# HeatPlatform_V1.net
KiCad netlist of a schematic drawn in Altium Designer
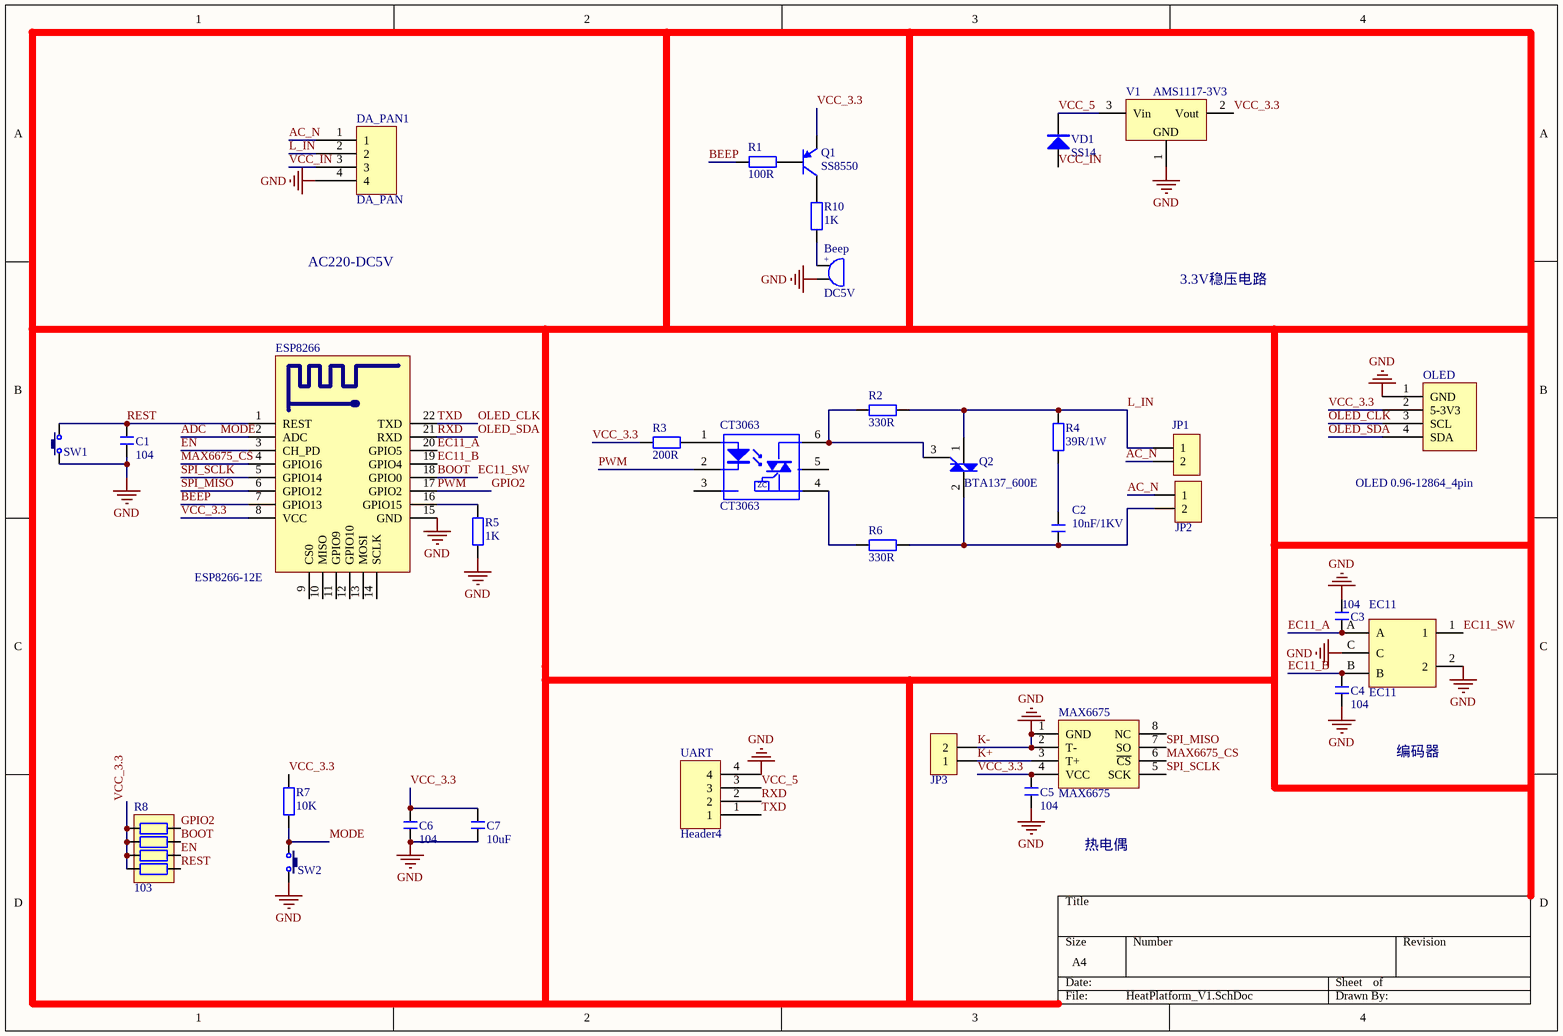
[diagram p0: HeatPlatform_V1.SchDoc]

(export (version "E")
  (design (tool "Eeschema 10.0.6"))
  (components
    (comp (ref "Beep")
      (value "DC5V")
      (footprint "BEEP 5x9x5.5")
      (description "蜂鸣器")
      (fields (field (name "版权归属") "源创客"))
      (libsource (lib "HeatPlatform") (part "BEEP"))
    )
    (comp (ref "C1")
      (value "104")
      (footprint "C 0603")
      (description "无极性贴片电容")
      (fields (field (name "版权归属") "源创客"))
      (libsource (lib "HeatPlatform") (part "C"))
    )
    (comp (ref "C2")
      (value "10nF/1KV")
      (footprint "C 1210_L")
      (description "无极性贴片电容")
      (fields (field (name "版权归属") "源创客"))
      (libsource (lib "HeatPlatform") (part "C"))
    )
    (comp (ref "C3")
      (value "104")
      (footprint "C 0603")
      (description "无极性贴片电容")
      (fields (field (name "版权归属") "源创客"))
      (libsource (lib "HeatPlatform") (part "C"))
    )
    (comp (ref "C4")
      (value "104")
      (footprint "C 0603")
      (description "无极性贴片电容")
      (fields (field (name "版权归属") "源创客"))
      (libsource (lib "HeatPlatform") (part "C"))
    )
    (comp (ref "C5")
      (value "104")
      (footprint "C 0603")
      (description "无极性贴片电容")
      (fields (field (name "版权归属") "源创客"))
      (libsource (lib "HeatPlatform") (part "C"))
    )
    (comp (ref "C6")
      (value "104")
      (footprint "C 0603")
      (description "无极性贴片电容")
      (fields (field (name "版权归属") "源创客"))
      (libsource (lib "HeatPlatform") (part "C"))
    )
    (comp (ref "C7")
      (value "10uF")
      (footprint "C 0603")
      (description "无极性贴片电容")
      (fields (field (name "版权归属") "源创客"))
      (libsource (lib "HeatPlatform") (part "C"))
    )
    (comp (ref "CT3063")
      (value "CT3063")
      (footprint "SMD-6")
      (description "线性光耦（过零检测）")
      (fields (field (name "版权归属") "源创客"))
      (libsource (lib "HeatPlatform") (part "CT3063"))
    )
    (comp (ref "DA_PAN1")
      (value "DA_PAN")
      (footprint "DA_PAN")
      (libsource (lib "HeatPlatform") (part "DA_PAN"))
    )
    (comp (ref "EC11")
      (value "EC11")
      (footprint "EC11")
      (description "数字开关编码器")
      (fields (field (name "版权归属") "源创客"))
      (libsource (lib "HeatPlatform") (part "EC11"))
    )
    (comp (ref "ESP8266")
      (value "ESP8266-12E")
      (footprint "ESP_12E")
      (description "串口 WIFI模块，ESP-12E")
      (fields (field (name "版权归属") "源创客"))
      (libsource (lib "HeatPlatform") (part "ESP8266-12E"))
    )
    (comp (ref "JP1")
      (value "HDR-1X2")
      (footprint "HDR-1X2")
      (description "2P接插件")
      (fields (field (name "版权归属") "源创客"))
      (libsource (lib "") (part "Header 2_1"))
    )
    (comp (ref "JP2")
      (value "HDR-1X2")
      (footprint "HDR-1X2")
      (description "2P接插件")
      (fields (field (name "版权归属") "源创客"))
      (libsource (lib "") (part "Header 2_1"))
    )
    (comp (ref "JP3")
      (value "HDR-1X2")
      (footprint "HDR-1X2")
      (description "2P接插件")
      (fields (field (name "版权归属") "源创客"))
      (libsource (lib "HeatPlatform") (part "Header 2"))
    )
    (comp (ref "MAX6675")
      (value "MAX6675")
      (footprint "SOP8_L")
      (description "K型热电偶检测芯片")
      (fields (field (name "版权归属") "源创客"))
      (libsource (lib "HeatPlatform") (part "MAX6675"))
    )
    (comp (ref "OLED")
      (value "OLED 0.96-12864_4pin")
      (footprint "OLED 0.96-12864_4pin")
      (description "12864 点阵屏")
      (libsource (lib "HeatPlatform") (part "OLED 0.96-12864_4pin"))
    )
    (comp (ref "Q1")
      (value "SS8550")
      (footprint "SOT23-3L")
      (description "高频放大-PNP型")
      (fields (field (name "版权归属") "源创客"))
      (libsource (lib "HeatPlatform") (part "8550-SMD"))
    )
    (comp (ref "Q2")
      (value "BTA137_600E")
      (footprint "TO252")
      (description "双向可控硅")
      (fields (field (name "版权归属") "源创客"))
      (libsource (lib "HeatPlatform") (part "BTA12_600"))
    )
    (comp (ref "R1")
      (value "100R")
      (footprint "R 0603")
      (description "贴片电阻")
      (fields (field (name "版权归属") "源创客"))
      (libsource (lib "HeatPlatform") (part "R"))
    )
    (comp (ref "R2")
      (value "330R")
      (footprint "R 0603")
      (description "贴片电阻")
      (fields (field (name "版权归属") "源创客"))
      (libsource (lib "HeatPlatform") (part "R"))
    )
    (comp (ref "R3")
      (value "200R")
      (footprint "R 0603")
      (description "贴片电阻")
      (fields (field (name "版权归属") "源创客"))
      (libsource (lib "HeatPlatform") (part "R"))
    )
    (comp (ref "R4")
      (value "39R/1W")
      (footprint "R 2512_L")
      (description "贴片电阻")
      (fields (field (name "版权归属") "源创客"))
      (libsource (lib "HeatPlatform") (part "R"))
    )
    (comp (ref "R5")
      (value "1K")
      (footprint "R 0603")
      (description "贴片电阻")
      (fields (field (name "版权归属") "源创客"))
      (libsource (lib "HeatPlatform") (part "R"))
    )
    (comp (ref "R6")
      (value "330R")
      (footprint "R 0603")
      (description "贴片电阻")
      (fields (field (name "版权归属") "源创客"))
      (libsource (lib "HeatPlatform") (part "R"))
    )
    (comp (ref "R7")
      (value "10K")
      (footprint "R 0603")
      (description "贴片电阻")
      (fields (field (name "版权归属") "源创客"))
      (libsource (lib "HeatPlatform") (part "R"))
    )
    (comp (ref "R8")
      (value "103")
      (footprint "RCA-8P4R-0603")
      (description "贴片网络排阻")
      (fields (field (name "版权归属") "源创客"))
      (libsource (lib "HeatPlatform") (part "R-8P4R"))
    )
    (comp (ref "R10")
      (value "1K")
      (footprint "R 0603")
      (description "贴片电阻")
      (fields (field (name "版权归属") "源创客"))
      (libsource (lib "HeatPlatform") (part "R"))
    )
    (comp (ref "SW1")
      (value "3*4*2")
      (footprint "TSW SMD-3*4*2")
      (description "3x4轻触开关")
      (fields (field (name "版权归属") "源创客"))
      (libsource (lib "") (part "TSW 3x4_1"))
    )
    (comp (ref "SW2")
      (value "3*4*2")
      (footprint "TSW SMD-3*4*2")
      (description "3x4轻触开关")
      (fields (field (name "版权归属") "源创客"))
      (libsource (lib "HeatPlatform") (part "TSW 3x4"))
    )
    (comp (ref "UART")
      (value "Header4")
      (footprint "HDR2.54-LI-4P")
      (libsource (lib "HeatPlatform") (part "Header4"))
    )
    (comp (ref "V1")
      (value "AMS1117-3V3")
      (footprint "SOT223_L")
      (description "三端稳压芯片")
      (fields (field (name "版权归属") "源创客"))
      (libsource (lib "HeatPlatform") (part "AMS1117"))
    )
    (comp (ref "VD1")
      (value "SS14")
      (footprint "SMA")
      (description "肖特基二极管")
      (fields (field (name "版权归属") "源创客"))
      (libsource (lib "HeatPlatform") (part "SS14"))
    )
  )
  (nets
    (net (code "1") (name "/AC_N") (class "Default")
      (node (ref "DA_PAN1") (pin "1") (pinfunction "1_1") (pintype "passive"))
      (node (ref "JP1") (pin "2") (pinfunction "2_2") (pintype "passive"))
      (node (ref "JP2") (pin "1") (pinfunction "1_1") (pintype "passive"))
    )
    (net (code "2") (name "/ADC") (class "Default")
      (node (ref "ESP8266") (pin "2") (pinfunction "ADC_2") (pintype "passive"))
      (node (ref "R7") (pin "1") (pinfunction "1_1") (pintype "passive"))
      (node (ref "SW2") (pin "1") (pinfunction "1_1") (pintype "passive"))
    )
    (net (code "3") (name "/BEEP") (class "Default")
      (node (ref "ESP8266") (pin "7") (pinfunction "GPIO13_7") (pintype "passive"))
      (node (ref "R1") (pin "1") (pinfunction "1_1") (pintype "passive"))
    )
    (net (code "4") (name "/BOOT") (class "Default")
      (node (ref "EC11") (pin "1") (pinfunction "1_1") (pintype "passive"))
      (node (ref "ESP8266") (pin "18") (pinfunction "GPIO0_18") (pintype "passive"))
      (node (ref "R8") (pin "7") (pinfunction "7_7") (pintype "passive"))
    )
    (net (code "5") (name "/EC11_A") (class "Default")
      (node (ref "C3") (pin "1") (pinfunction "1_1") (pintype "passive"))
      (node (ref "EC11") (pin "A") (pinfunction "A_A") (pintype "passive"))
      (node (ref "ESP8266") (pin "20") (pinfunction "GPIO5_20") (pintype "passive"))
    )
    (net (code "6") (name "/EC11_B") (class "Default")
      (node (ref "C4") (pin "2") (pinfunction "2_2") (pintype "passive"))
      (node (ref "EC11") (pin "B") (pinfunction "B_B") (pintype "passive"))
      (node (ref "ESP8266") (pin "19") (pinfunction "GPIO4_19") (pintype "passive"))
    )
    (net (code "7") (name "/EN") (class "Default")
      (node (ref "ESP8266") (pin "3") (pinfunction "CH_PD_3") (pintype "passive"))
      (node (ref "R8") (pin "6") (pinfunction "6_6") (pintype "passive"))
    )
    (net (code "8") (name "/GPIO2") (class "Default")
      (node (ref "CT3063") (pin "2") (pinfunction "C_2") (pintype "passive"))
      (node (ref "ESP8266") (pin "17") (pinfunction "GPIO2_17") (pintype "passive"))
      (node (ref "R8") (pin "8") (pinfunction "8_8") (pintype "passive"))
    )
    (net (code "9") (name "/K+") (class "Default")
      (node (ref "JP3") (pin "1") (pinfunction "1_1") (pintype "passive"))
      (node (ref "MAX6675") (pin "3") (pinfunction "T+_3") (pintype "passive"))
    )
    (net (code "10") (name "/L_IN") (class "Default")
      (node (ref "DA_PAN1") (pin "2") (pinfunction "2_2") (pintype "passive"))
      (node (ref "JP1") (pin "1") (pinfunction "1_1") (pintype "passive"))
      (node (ref "Q2") (pin "1") (pinfunction "A1_1") (pintype "passive"))
      (node (ref "R2") (pin "2") (pinfunction "2_2") (pintype "passive"))
      (node (ref "R4") (pin "2") (pinfunction "2_2") (pintype "passive"))
    )
    (net (code "11") (name "/MAX6675_CS") (class "Default")
      (node (ref "ESP8266") (pin "4") (pinfunction "GPIO16_4") (pintype "passive"))
      (node (ref "MAX6675") (pin "6") (pinfunction "~{CS}_6") (pintype "passive"))
    )
    (net (code "12") (name "/OLED_CLK") (class "Default")
      (node (ref "ESP8266") (pin "22") (pinfunction "TXD_22") (pintype "passive"))
      (node (ref "OLED") (pin "3") (pinfunction "SCL_3") (pintype "passive"))
      (node (ref "UART") (pin "1") (pinfunction "1_1") (pintype "passive"))
    )
    (net (code "13") (name "/OLED_SDA") (class "Default")
      (node (ref "ESP8266") (pin "21") (pinfunction "RXD_21") (pintype "passive"))
      (node (ref "OLED") (pin "4") (pinfunction "SDA_4") (pintype "passive"))
      (node (ref "UART") (pin "2") (pinfunction "2_2") (pintype "passive"))
    )
    (net (code "14") (name "/REST") (class "Default")
      (node (ref "C1") (pin "2") (pinfunction "2_2") (pintype "passive"))
      (node (ref "ESP8266") (pin "1") (pinfunction "REST_1") (pintype "passive"))
      (node (ref "R8") (pin "5") (pinfunction "5_5") (pintype "passive"))
      (node (ref "SW1") (pin "2") (pinfunction "2_2") (pintype "passive"))
    )
    (net (code "15") (name "/SPI_MISO") (class "Default")
      (node (ref "ESP8266") (pin "6") (pinfunction "GPIO12_6") (pintype "passive"))
      (node (ref "MAX6675") (pin "7") (pinfunction "SO_7") (pintype "passive"))
    )
    (net (code "16") (name "/SPI_SCLK") (class "Default")
      (node (ref "ESP8266") (pin "5") (pinfunction "GPIO14_5") (pintype "passive"))
      (node (ref "MAX6675") (pin "5") (pinfunction "SCK_5") (pintype "passive"))
    )
    (net (code "17") (name "/VCC_3.3") (class "Default")
      (node (ref "C5") (pin "2") (pinfunction "2_2") (pintype "passive"))
      (node (ref "C6") (pin "2") (pinfunction "2_2") (pintype "passive"))
      (node (ref "C7") (pin "2") (pinfunction "2_2") (pintype "passive"))
      (node (ref "ESP8266") (pin "8") (pinfunction "VCC_8") (pintype "passive"))
      (node (ref "MAX6675") (pin "4") (pinfunction "VCC_4") (pintype "passive"))
      (node (ref "OLED") (pin "2") (pinfunction "5-3V3_2") (pintype "passive"))
      (node (ref "Q1") (pin "2") (pinfunction "E_2") (pintype "passive"))
      (node (ref "R3") (pin "2") (pinfunction "2_2") (pintype "passive"))
      (node (ref "R7") (pin "2") (pinfunction "2_2") (pintype "passive"))
      (node (ref "R8") (pin "1") (pinfunction "1_1") (pintype "passive"))
      (node (ref "R8") (pin "2") (pinfunction "2_2") (pintype "passive"))
      (node (ref "R8") (pin "3") (pinfunction "3_3") (pintype "passive"))
      (node (ref "R8") (pin "4") (pinfunction "4_4") (pintype "passive"))
      (node (ref "V1") (pin "2") (pinfunction "Vout_2") (pintype "passive"))
    )
    (net (code "18") (name "/VCC_5") (class "Default")
      (node (ref "UART") (pin "3") (pinfunction "3_3") (pintype "passive"))
      (node (ref "V1") (pin "3") (pinfunction "Vin_3") (pintype "passive"))
      (node (ref "VD1") (pin "2") (pinfunction "K_2") (pintype "passive"))
    )
    (net (code "19") (name "/VCC_IN") (class "Default")
      (node (ref "DA_PAN1") (pin "3") (pinfunction "3_3") (pintype "passive"))
      (node (ref "VD1") (pin "1") (pinfunction "A_1") (pintype "passive"))
    )
    (net (code "20") (name "GND") (class "Default")
      (node (ref "Beep") (pin "2") (pinfunction "2_2") (pintype "passive"))
      (node (ref "C1") (pin "1") (pinfunction "1_1") (pintype "passive"))
      (node (ref "C3") (pin "2") (pinfunction "2_2") (pintype "passive"))
      (node (ref "C4") (pin "1") (pinfunction "1_1") (pintype "passive"))
      (node (ref "C5") (pin "1") (pinfunction "1_1") (pintype "passive"))
      (node (ref "C6") (pin "1") (pinfunction "1_1") (pintype "passive"))
      (node (ref "C7") (pin "1") (pinfunction "1_1") (pintype "passive"))
      (node (ref "DA_PAN1") (pin "4") (pinfunction "4_4") (pintype "passive"))
      (node (ref "EC11") (pin "2") (pinfunction "2_2") (pintype "passive"))
      (node (ref "EC11") (pin "C") (pinfunction "C_C") (pintype "passive"))
      (node (ref "ESP8266") (pin "15") (pinfunction "GND_15") (pintype "passive"))
      (node (ref "JP3") (pin "2") (pinfunction "2_2") (pintype "passive"))
      (node (ref "MAX6675") (pin "1") (pinfunction "GND_1") (pintype "passive"))
      (node (ref "MAX6675") (pin "2") (pinfunction "T-_2") (pintype "passive"))
      (node (ref "OLED") (pin "1") (pinfunction "GND_1") (pintype "passive"))
      (node (ref "R5") (pin "1") (pinfunction "1_1") (pintype "passive"))
      (node (ref "SW1") (pin "1") (pinfunction "1_1") (pintype "passive"))
      (node (ref "SW2") (pin "2") (pinfunction "2_2") (pintype "passive"))
      (node (ref "UART") (pin "4") (pinfunction "4_4") (pintype "passive"))
      (node (ref "V1") (pin "1") (pinfunction "GND_1") (pintype "passive"))
    )
    (net (code "21") (name "Net-(Beep-Pad1)") (class "Default")
      (node (ref "Beep") (pin "1") (pinfunction "1_1") (pintype "passive"))
      (node (ref "R10") (pin "1") (pinfunction "1_1") (pintype "passive"))
    )
    (net (code "22") (name "Net-(C2-Pad2)") (class "Default")
      (node (ref "C2") (pin "2") (pinfunction "2_2") (pintype "passive"))
      (node (ref "R4") (pin "1") (pinfunction "1_1") (pintype "passive"))
    )
    (net (code "23") (name "Net-(CT3063-A)") (class "Default")
      (node (ref "CT3063") (pin "1") (pinfunction "A_1") (pintype "passive"))
      (node (ref "R3") (pin "1") (pinfunction "1_1") (pintype "passive"))
    )
    (net (code "24") (name "Net-(CT3063-MT1)") (class "Default")
      (node (ref "CT3063") (pin "6") (pinfunction "MT1_6") (pintype "passive"))
      (node (ref "Q2") (pin "3") (pinfunction "G_3") (pintype "passive"))
      (node (ref "R2") (pin "1") (pinfunction "1_1") (pintype "passive"))
    )
    (net (code "25") (name "Net-(CT3063-MT2)") (class "Default")
      (node (ref "CT3063") (pin "4") (pinfunction "MT2_4") (pintype "passive"))
      (node (ref "R6") (pin "2") (pinfunction "2_2") (pintype "passive"))
    )
    (net (code "26") (name "Net-(ESP8266-GPIO15)") (class "Default")
      (node (ref "ESP8266") (pin "16") (pinfunction "GPIO15_16") (pintype "passive"))
      (node (ref "R5") (pin "2") (pinfunction "2_2") (pintype "passive"))
    )
    (net (code "27") (name "Net-(Q1-B)") (class "Default")
      (node (ref "Q1") (pin "1") (pinfunction "B_1") (pintype "passive"))
      (node (ref "R1") (pin "2") (pinfunction "2_2") (pintype "passive"))
    )
    (net (code "28") (name "Net-(Q1-C)") (class "Default")
      (node (ref "Q1") (pin "3") (pinfunction "C_3") (pintype "passive"))
      (node (ref "R10") (pin "2") (pinfunction "2_2") (pintype "passive"))
    )
    (net (code "29") (name "Net-(Q2-A2)") (class "Default")
      (node (ref "C2") (pin "1") (pinfunction "1_1") (pintype "passive"))
      (node (ref "JP2") (pin "2") (pinfunction "2_2") (pintype "passive"))
      (node (ref "Q2") (pin "2") (pinfunction "A2_2") (pintype "passive"))
      (node (ref "R6") (pin "1") (pinfunction "1_1") (pintype "passive"))
    )
    (net (code "30") (name "unconnected-(CT3063-NC-Pad3)") (class "Default")
      (node (ref "CT3063") (pin "3") (pinfunction "NC_3") (pintype "passive"))
    )
    (net (code "31") (name "unconnected-(CT3063-NC-Pad5)") (class "Default")
      (node (ref "CT3063") (pin "5") (pinfunction "NC_5") (pintype "passive"))
    )
    (net (code "32") (name "unconnected-(ESP8266-CS0-Pad9)") (class "Default")
      (node (ref "ESP8266") (pin "9") (pinfunction "CS0_9") (pintype "passive"))
    )
    (net (code "33") (name "unconnected-(ESP8266-GPIO9-Pad11)") (class "Default")
      (node (ref "ESP8266") (pin "11") (pinfunction "GPIO9_11") (pintype "passive"))
    )
    (net (code "34") (name "unconnected-(ESP8266-GPIO10-Pad12)") (class "Default")
      (node (ref "ESP8266") (pin "12") (pinfunction "GPIO10_12") (pintype "passive"))
    )
    (net (code "35") (name "unconnected-(ESP8266-MISO-Pad10)") (class "Default")
      (node (ref "ESP8266") (pin "10") (pinfunction "MISO_10") (pintype "passive"))
    )
    (net (code "36") (name "unconnected-(ESP8266-MOSI-Pad13)") (class "Default")
      (node (ref "ESP8266") (pin "13") (pinfunction "MOSI_13") (pintype "passive"))
    )
    (net (code "37") (name "unconnected-(ESP8266-SCLK-Pad14)") (class "Default")
      (node (ref "ESP8266") (pin "14") (pinfunction "SCLK_14") (pintype "passive"))
    )
    (net (code "38") (name "unconnected-(MAX6675-NC-Pad8)") (class "Default")
      (node (ref "MAX6675") (pin "8") (pinfunction "NC_8") (pintype "passive"))
    )
  )
)
